# Modules.net
KiCad netlist of a schematic drawn in Altium Designer
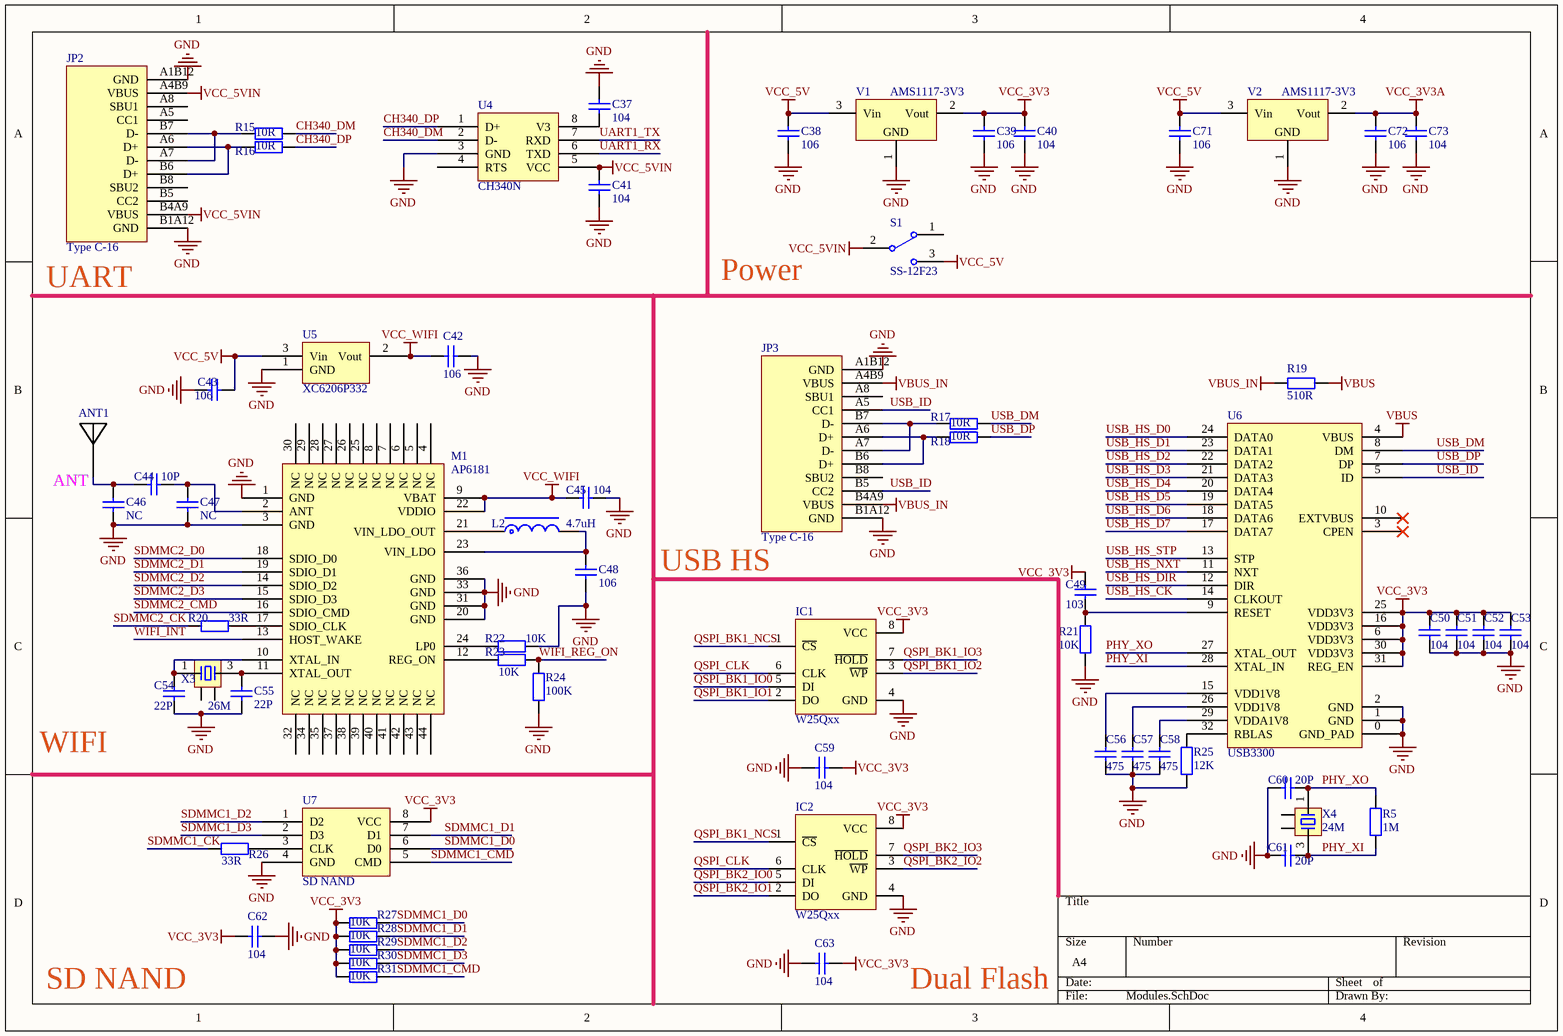
[diagram p0: Modules.SchDoc]

(export (version "E")
  (design (tool "Eeschema 10.0.6"))
  (components
    (comp (ref "ANT1") (value "ANT_SMD") (footprint "2.4G ANT") (libsource (lib "MySchlib") (part "ANT_SMD")))
    (comp (ref "C37")
      (value "104")
      (footprint "C0402_M")
      (description "贴片电容/MLCC电容")
      (libsource (lib "0.1 - 电阻-电容-电感-晶振-晶体-磁珠-电位器-法拉电容-馈通电容") (part "C"))
    )
    (comp (ref "C38")
      (value "106")
      (footprint "C1206_M")
      (description "贴片电容/MLCC电容")
      (libsource (lib "0.1 - 电阻-电容-电感-晶振-晶体-磁珠-电位器-法拉电容-馈通电容") (part "C"))
    )
    (comp (ref "C39")
      (value "106")
      (footprint "C0402_M")
      (description "贴片电容/MLCC电容")
      (libsource (lib "0.1 - 电阻-电容-电感-晶振-晶体-磁珠-电位器-法拉电容-馈通电容") (part "C"))
    )
    (comp (ref "C40")
      (value "104")
      (footprint "C0402_M")
      (description "贴片电容/MLCC电容")
      (libsource (lib "0.1 - 电阻-电容-电感-晶振-晶体-磁珠-电位器-法拉电容-馈通电容") (part "C"))
    )
    (comp (ref "C41")
      (value "104")
      (footprint "C0402_M")
      (description "贴片电容/MLCC电容")
      (libsource (lib "0.1 - 电阻-电容-电感-晶振-晶体-磁珠-电位器-法拉电容-馈通电容") (part "C"))
    )
    (comp (ref "C42")
      (value "106")
      (footprint "C0402_M")
      (description "贴片电容/MLCC电容")
      (libsource (lib "0.1 - 电阻-电容-电感-晶振-晶体-磁珠-电位器-法拉电容-馈通电容") (part "C"))
    )
    (comp (ref "C43")
      (value "106")
      (footprint "C0402_M")
      (description "贴片电容/MLCC电容")
      (libsource (lib "0.1 - 电阻-电容-电感-晶振-晶体-磁珠-电位器-法拉电容-馈通电容") (part "C"))
    )
    (comp (ref "C44")
      (value "10P")
      (footprint "C0402_M")
      (description "贴片电容/MLCC电容")
      (libsource (lib "0.1 - 电阻-电容-电感-晶振-晶体-磁珠-电位器-法拉电容-馈通电容") (part "C"))
    )
    (comp (ref "C45")
      (value "104")
      (footprint "C0402_M")
      (description "贴片电容/MLCC电容")
      (libsource (lib "0.1 - 电阻-电容-电感-晶振-晶体-磁珠-电位器-法拉电容-馈通电容") (part "C"))
    )
    (comp (ref "C46")
      (value "NC")
      (footprint "C0402_M")
      (description "贴片电容/MLCC电容")
      (libsource (lib "0.1 - 电阻-电容-电感-晶振-晶体-磁珠-电位器-法拉电容-馈通电容") (part "C"))
    )
    (comp (ref "C47")
      (value "NC")
      (footprint "C0402_M")
      (description "贴片电容/MLCC电容")
      (libsource (lib "0.1 - 电阻-电容-电感-晶振-晶体-磁珠-电位器-法拉电容-馈通电容") (part "C"))
    )
    (comp (ref "C48")
      (value "106")
      (footprint "C0402_M")
      (description "贴片电容/MLCC电容")
      (libsource (lib "0.1 - 电阻-电容-电感-晶振-晶体-磁珠-电位器-法拉电容-馈通电容") (part "C"))
    )
    (comp (ref "C49")
      (value "103")
      (footprint "C0402_M")
      (description "贴片电容/MLCC电容")
      (libsource (lib "0.1 - 电阻-电容-电感-晶振-晶体-磁珠-电位器-法拉电容-馈通电容") (part "C"))
    )
    (comp (ref "C50")
      (value "104")
      (footprint "C0402_M")
      (description "贴片电容/MLCC电容")
      (libsource (lib "0.1 - 电阻-电容-电感-晶振-晶体-磁珠-电位器-法拉电容-馈通电容") (part "C"))
    )
    (comp (ref "C51")
      (value "104")
      (footprint "C0402_M")
      (description "贴片电容/MLCC电容")
      (libsource (lib "0.1 - 电阻-电容-电感-晶振-晶体-磁珠-电位器-法拉电容-馈通电容") (part "C"))
    )
    (comp (ref "C52")
      (value "104")
      (footprint "C0402_M")
      (description "贴片电容/MLCC电容")
      (libsource (lib "0.1 - 电阻-电容-电感-晶振-晶体-磁珠-电位器-法拉电容-馈通电容") (part "C"))
    )
    (comp (ref "C53")
      (value "104")
      (footprint "C0402_M")
      (description "贴片电容/MLCC电容")
      (libsource (lib "0.1 - 电阻-电容-电感-晶振-晶体-磁珠-电位器-法拉电容-馈通电容") (part "C"))
    )
    (comp (ref "C54")
      (value "22P")
      (footprint "C0402_M")
      (description "贴片电容/MLCC电容")
      (libsource (lib "0.1 - 电阻-电容-电感-晶振-晶体-磁珠-电位器-法拉电容-馈通电容") (part "C"))
    )
    (comp (ref "C55")
      (value "22P")
      (footprint "C0402_M")
      (description "贴片电容/MLCC电容")
      (libsource (lib "0.1 - 电阻-电容-电感-晶振-晶体-磁珠-电位器-法拉电容-馈通电容") (part "C"))
    )
    (comp (ref "C56")
      (value "475")
      (footprint "C0402_M")
      (description "贴片电容/MLCC电容")
      (libsource (lib "0.1 - 电阻-电容-电感-晶振-晶体-磁珠-电位器-法拉电容-馈通电容") (part "C"))
    )
    (comp (ref "C57")
      (value "475")
      (footprint "C0402_M")
      (description "贴片电容/MLCC电容")
      (libsource (lib "0.1 - 电阻-电容-电感-晶振-晶体-磁珠-电位器-法拉电容-馈通电容") (part "C"))
    )
    (comp (ref "C58")
      (value "475")
      (footprint "C0402_M")
      (description "贴片电容/MLCC电容")
      (libsource (lib "0.1 - 电阻-电容-电感-晶振-晶体-磁珠-电位器-法拉电容-馈通电容") (part "C"))
    )
    (comp (ref "C59")
      (value "104")
      (footprint "C0402_M")
      (description "贴片电容/MLCC电容")
      (libsource (lib "0.1 - 电阻-电容-电感-晶振-晶体-磁珠-电位器-法拉电容-馈通电容") (part "C"))
    )
    (comp (ref "C60")
      (value "20P")
      (footprint "C0402_M")
      (description "贴片电容/MLCC电容")
      (libsource (lib "0.1 - 电阻-电容-电感-晶振-晶体-磁珠-电位器-法拉电容-馈通电容") (part "C"))
    )
    (comp (ref "C61")
      (value "20P")
      (footprint "C0402_M")
      (description "贴片电容/MLCC电容")
      (libsource (lib "0.1 - 电阻-电容-电感-晶振-晶体-磁珠-电位器-法拉电容-馈通电容") (part "C"))
    )
    (comp (ref "C62")
      (value "104")
      (footprint "C0402_M")
      (description "贴片电容/MLCC电容")
      (libsource (lib "0.1 - 电阻-电容-电感-晶振-晶体-磁珠-电位器-法拉电容-馈通电容") (part "C"))
    )
    (comp (ref "C63")
      (value "104")
      (footprint "C0402_M")
      (description "贴片电容/MLCC电容")
      (libsource (lib "0.1 - 电阻-电容-电感-晶振-晶体-磁珠-电位器-法拉电容-馈通电容") (part "C"))
    )
    (comp (ref "C71")
      (value "106")
      (footprint "C1206_M")
      (description "贴片电容/MLCC电容")
      (libsource (lib "0.1 - 电阻-电容-电感-晶振-晶体-磁珠-电位器-法拉电容-馈通电容") (part "C"))
    )
    (comp (ref "C72")
      (value "106")
      (footprint "C0402_M")
      (description "贴片电容/MLCC电容")
      (libsource (lib "0.1 - 电阻-电容-电感-晶振-晶体-磁珠-电位器-法拉电容-馈通电容") (part "C"))
    )
    (comp (ref "C73")
      (value "104")
      (footprint "C0402_M")
      (description "贴片电容/MLCC电容")
      (libsource (lib "0.1 - 电阻-电容-电感-晶振-晶体-磁珠-电位器-法拉电容-馈通电容") (part "C"))
    )
    (comp (ref "IC1")
      (value "W25Qxx")
      (footprint "SOP8W_N")
      (description "SPI Flash")
      (fields (field (name "版权归属") "封装库来自淘宝 ID：黄晶宝石"))
      (libsource (lib "1.0 - 常见芯片") (part "W25Q"))
    )
    (comp (ref "IC2")
      (value "W25Qxx")
      (footprint "SOP8W_N")
      (description "SPI Flash")
      (fields (field (name "版权归属") "封装库来自淘宝 ID：黄晶宝石"))
      (libsource (lib "1.0 - 常见芯片") (part "W25Q"))
    )
    (comp (ref "JP2") (value "Type C-16") (footprint "TypeC16") (libsource (lib "我的原理图库") (part "Type C-16")))
    (comp (ref "JP3") (value "Type C-16") (footprint "TypeC16") (libsource (lib "我的原理图库") (part "Type C-16")))
    (comp (ref "L2")
      (value "4.7uH")
      (footprint "L1210")
      (description "太诱-NR磁胶电感")
      (libsource (lib "0.1 - 电阻-电容-电感-晶振-晶体-磁珠-电位器-法拉电容-馈通电容") (part "L-NR"))
    )
    (comp (ref "M1")
      (value "AP6181")
      (footprint "AP6181")
      (description "SDIO WIFI模块")
      (libsource (lib "MySchlib") (part "AP6181"))
    )
    (comp (ref "R5")
      (value "1M")
      (footprint "R0402_M")
      (description "贴片电阻")
      (libsource (lib "0.1 - 电阻-电容-电感-晶振-晶体-磁珠-电位器-法拉电容-馈通电容") (part "R"))
    )
    (comp (ref "R15")
      (value "10R")
      (footprint "R0402_M")
      (description "贴片电阻")
      (libsource (lib "0.1 - 电阻-电容-电感-晶振-晶体-磁珠-电位器-法拉电容-馈通电容") (part "R"))
    )
    (comp (ref "R16")
      (value "10R")
      (footprint "R0402_M")
      (description "贴片电阻")
      (libsource (lib "0.1 - 电阻-电容-电感-晶振-晶体-磁珠-电位器-法拉电容-馈通电容") (part "R"))
    )
    (comp (ref "R17")
      (value "10R")
      (footprint "R0402_M")
      (description "贴片电阻")
      (libsource (lib "0.1 - 电阻-电容-电感-晶振-晶体-磁珠-电位器-法拉电容-馈通电容") (part "R"))
    )
    (comp (ref "R18")
      (value "10R")
      (footprint "R0402_M")
      (description "贴片电阻")
      (libsource (lib "0.1 - 电阻-电容-电感-晶振-晶体-磁珠-电位器-法拉电容-馈通电容") (part "R"))
    )
    (comp (ref "R19")
      (value "510R")
      (footprint "R0603_M")
      (description "贴片电阻")
      (libsource (lib "0.1 - 电阻-电容-电感-晶振-晶体-磁珠-电位器-法拉电容-馈通电容") (part "R"))
    )
    (comp (ref "R20")
      (value "33R")
      (footprint "R0402_M")
      (description "贴片电阻")
      (libsource (lib "0.1 - 电阻-电容-电感-晶振-晶体-磁珠-电位器-法拉电容-馈通电容") (part "R"))
    )
    (comp (ref "R21")
      (value "10K")
      (footprint "R0402_M")
      (description "贴片电阻")
      (libsource (lib "0.1 - 电阻-电容-电感-晶振-晶体-磁珠-电位器-法拉电容-馈通电容") (part "R"))
    )
    (comp (ref "R22")
      (value "10K")
      (footprint "R0402_M")
      (description "贴片电阻")
      (libsource (lib "0.1 - 电阻-电容-电感-晶振-晶体-磁珠-电位器-法拉电容-馈通电容") (part "R"))
    )
    (comp (ref "R23")
      (value "10K")
      (footprint "R0402_M")
      (description "贴片电阻")
      (libsource (lib "0.1 - 电阻-电容-电感-晶振-晶体-磁珠-电位器-法拉电容-馈通电容") (part "R"))
    )
    (comp (ref "R24")
      (value "100K")
      (footprint "R0402_M")
      (description "贴片电阻")
      (libsource (lib "0.1 - 电阻-电容-电感-晶振-晶体-磁珠-电位器-法拉电容-馈通电容") (part "R"))
    )
    (comp (ref "R25")
      (value "12K")
      (footprint "R0402_M")
      (description "贴片电阻")
      (libsource (lib "0.1 - 电阻-电容-电感-晶振-晶体-磁珠-电位器-法拉电容-馈通电容") (part "R"))
    )
    (comp (ref "R26")
      (value "33R")
      (footprint "R0402_M")
      (description "贴片电阻")
      (libsource (lib "0.1 - 电阻-电容-电感-晶振-晶体-磁珠-电位器-法拉电容-馈通电容") (part "R"))
    )
    (comp (ref "R27")
      (value "10K")
      (footprint "R0402_M")
      (description "贴片电阻")
      (libsource (lib "0.1 - 电阻-电容-电感-晶振-晶体-磁珠-电位器-法拉电容-馈通电容") (part "R"))
    )
    (comp (ref "R28")
      (value "10K")
      (footprint "R0402_M")
      (description "贴片电阻")
      (libsource (lib "0.1 - 电阻-电容-电感-晶振-晶体-磁珠-电位器-法拉电容-馈通电容") (part "R"))
    )
    (comp (ref "R29")
      (value "10K")
      (footprint "R0402_M")
      (description "贴片电阻")
      (libsource (lib "0.1 - 电阻-电容-电感-晶振-晶体-磁珠-电位器-法拉电容-馈通电容") (part "R"))
    )
    (comp (ref "R30")
      (value "10K")
      (footprint "R0402_M")
      (description "贴片电阻")
      (libsource (lib "0.1 - 电阻-电容-电感-晶振-晶体-磁珠-电位器-法拉电容-馈通电容") (part "R"))
    )
    (comp (ref "R31")
      (value "10K")
      (footprint "R0402_M")
      (description "贴片电阻")
      (libsource (lib "0.1 - 电阻-电容-电感-晶振-晶体-磁珠-电位器-法拉电容-馈通电容") (part "R"))
    )
    (comp (ref "S1")
      (value "SS-12F23")
      (footprint "MSK-12C01-07")
      (description "1路波动开关")
      (libsource (lib "0.5 - 按键_开关_蜂鸣器_保险丝_电池_测试点_Mark点_铜柱") (part "SSW-1P"))
    )
    (comp (ref "U4")
      (value "CH340N")
      (footprint "SOP8")
      (description "USB转UART芯片 8P")
      (libsource (lib "MySchlib") (part "CH340N"))
    )
    (comp (ref "U5")
      (value "XC6206P332")
      (footprint "SOT23-3N")
      (description "低压差LDO")
      (libsource (lib "MySchlib") (part "XC6206P332"))
    )
    (comp (ref "U6")
      (value "USB3300")
      (footprint "QFN32 5x5_M")
      (description "USB2.0 HS PHY")
      (libsource (lib "MySchlib") (part "USB3300"))
    )
    (comp (ref "U7")
      (value "SD NAND")
      (footprint "LGA8 6x8mm")
      (description "贴片式SD")
      (libsource (lib "MySchlib") (part "SD NAND"))
    )
    (comp (ref "V1")
      (value "AMS1117-3V3")
      (footprint "SOT89_N")
      (description "三端稳压芯片")
      (libsource (lib "0.7 - 电源类芯片") (part "AMS1117_SOT89"))
    )
    (comp (ref "V2")
      (value "AMS1117-3V3")
      (footprint "SOT89_N")
      (description "三端稳压芯片")
      (libsource (lib "0.7 - 电源类芯片") (part "AMS1117_SOT89"))
    )
    (comp (ref "X3")
      (value "26M")
      (footprint "XTAL-3225-4P")
      (description "4脚无源晶振(谐振器）")
      (libsource (lib "") (part "XTAL-4P_1"))
    )
    (comp (ref "X4")
      (value "24M")
      (footprint "XTAL-3225-4P")
      (description "4脚无源晶振(谐振器）")
      (libsource (lib "0.1 - 电阻-电容-电感-晶振-晶体-磁珠-电位器-法拉电容-馈通电容") (part "XTAL-4P"))
    )
  )
  (nets
    (net (code "1") (name "/CH340_DM") (class "Default")
      (node (ref "R15") (pin "1") (pinfunction "1_1") (pintype "passive"))
      (node (ref "U4") (pin "2") (pinfunction "D-_2") (pintype "passive"))
    )
    (net (code "2") (name "/CH340_DP") (class "Default")
      (node (ref "R16") (pin "1") (pinfunction "1_1") (pintype "passive"))
      (node (ref "U4") (pin "1") (pinfunction "D+_1") (pintype "passive"))
    )
    (net (code "3") (name "/PHY_XI") (class "Default")
      (node (ref "C61") (pin "2") (pinfunction "2_2") (pintype "passive"))
      (node (ref "R5") (pin "1") (pinfunction "1_1") (pintype "passive"))
      (node (ref "U6") (pin "28") (pinfunction "XTAL_IN_28") (pintype "passive"))
      (node (ref "X4") (pin "3") (pinfunction "3_3") (pintype "passive"))
    )
    (net (code "4") (name "/PHY_XO") (class "Default")
      (node (ref "C60") (pin "2") (pinfunction "2_2") (pintype "passive"))
      (node (ref "R5") (pin "2") (pinfunction "2_2") (pintype "passive"))
      (node (ref "U6") (pin "27") (pinfunction "XTAL_OUT_27") (pintype "passive"))
      (node (ref "X4") (pin "1") (pinfunction "1_1") (pintype "passive"))
    )
    (net (code "5") (name "/QSPI_BK1_IO0") (class "Default")
      (node (ref "IC1") (pin "5") (pinfunction "DI_5") (pintype "passive"))
    )
    (net (code "6") (name "/QSPI_BK1_IO1") (class "Default")
      (node (ref "IC1") (pin "2") (pinfunction "DO_2") (pintype "passive"))
    )
    (net (code "7") (name "/QSPI_BK1_IO2") (class "Default")
      (node (ref "IC1") (pin "3") (pinfunction "~{WP}_3") (pintype "passive"))
    )
    (net (code "8") (name "/QSPI_BK1_IO3") (class "Default")
      (node (ref "IC1") (pin "7") (pinfunction "~{HOLD}_7") (pintype "passive"))
    )
    (net (code "9") (name "/QSPI_BK1_NCS") (class "Default")
      (node (ref "IC1") (pin "1") (pinfunction "~{CS}_1") (pintype "passive"))
      (node (ref "IC2") (pin "1") (pinfunction "~{CS}_1") (pintype "passive"))
    )
    (net (code "10") (name "/QSPI_BK2_IO0") (class "Default")
      (node (ref "IC2") (pin "5") (pinfunction "DI_5") (pintype "passive"))
    )
    (net (code "11") (name "/QSPI_BK2_IO1") (class "Default")
      (node (ref "IC2") (pin "2") (pinfunction "DO_2") (pintype "passive"))
    )
    (net (code "12") (name "/QSPI_BK2_IO2") (class "Default")
      (node (ref "IC2") (pin "3") (pinfunction "~{WP}_3") (pintype "passive"))
    )
    (net (code "13") (name "/QSPI_BK2_IO3") (class "Default")
      (node (ref "IC2") (pin "7") (pinfunction "~{HOLD}_7") (pintype "passive"))
    )
    (net (code "14") (name "/QSPI_CLK") (class "Default")
      (node (ref "IC1") (pin "6") (pinfunction "CLK_6") (pintype "passive"))
      (node (ref "IC2") (pin "6") (pinfunction "CLK_6") (pintype "passive"))
    )
    (net (code "15") (name "/SDMMC1_CK") (class "Default")
      (node (ref "R26") (pin "2") (pinfunction "2_2") (pintype "passive"))
    )
    (net (code "16") (name "/SDMMC1_CMD") (class "Default")
      (node (ref "R31") (pin "1") (pinfunction "1_1") (pintype "passive"))
      (node (ref "U7") (pin "5") (pinfunction "CMD_5") (pintype "passive"))
    )
    (net (code "17") (name "/SDMMC1_D0") (class "Default")
      (node (ref "R27") (pin "1") (pinfunction "1_1") (pintype "passive"))
      (node (ref "U7") (pin "6") (pinfunction "D0_6") (pintype "passive"))
    )
    (net (code "18") (name "/SDMMC1_D1") (class "Default")
      (node (ref "R28") (pin "1") (pinfunction "1_1") (pintype "passive"))
      (node (ref "U7") (pin "7") (pinfunction "D1_7") (pintype "passive"))
    )
    (net (code "19") (name "/SDMMC1_D2") (class "Default")
      (node (ref "R29") (pin "1") (pinfunction "1_1") (pintype "passive"))
      (node (ref "U7") (pin "1") (pinfunction "D2_1") (pintype "passive"))
    )
    (net (code "20") (name "/SDMMC1_D3") (class "Default")
      (node (ref "R30") (pin "1") (pinfunction "1_1") (pintype "passive"))
      (node (ref "U7") (pin "2") (pinfunction "D3_2") (pintype "passive"))
    )
    (net (code "21") (name "/SDMMC2_CK") (class "Default")
      (node (ref "R20") (pin "2") (pinfunction "2_2") (pintype "passive"))
    )
    (net (code "22") (name "/SDMMC2_CMD") (class "Default")
      (node (ref "M1") (pin "16") (pinfunction "SDIO_CMD_16") (pintype "tri_state"))
    )
    (net (code "23") (name "/SDMMC2_D0") (class "Default")
      (node (ref "M1") (pin "18") (pinfunction "SDIO_D0_18") (pintype "tri_state"))
    )
    (net (code "24") (name "/SDMMC2_D1") (class "Default")
      (node (ref "M1") (pin "19") (pinfunction "SDIO_D1_19") (pintype "passive"))
    )
    (net (code "25") (name "/SDMMC2_D2") (class "Default")
      (node (ref "M1") (pin "14") (pinfunction "SDIO_D2_14") (pintype "tri_state"))
    )
    (net (code "26") (name "/SDMMC2_D3") (class "Default")
      (node (ref "M1") (pin "15") (pinfunction "SDIO_D3_15") (pintype "tri_state"))
    )
    (net (code "27") (name "/UART1_RX") (class "Default")
      (node (ref "U4") (pin "6") (pinfunction "TXD_6") (pintype "passive"))
    )
    (net (code "28") (name "/UART1_TX") (class "Default")
      (node (ref "U4") (pin "7") (pinfunction "RXD_7") (pintype "passive"))
    )
    (net (code "29") (name "/USB_DM") (class "Default")
      (node (ref "R17") (pin "1") (pinfunction "1_1") (pintype "passive"))
      (node (ref "U6") (pin "8") (pinfunction "DM_8") (pintype "passive"))
    )
    (net (code "30") (name "/USB_DP") (class "Default")
      (node (ref "R18") (pin "1") (pinfunction "1_1") (pintype "passive"))
      (node (ref "U6") (pin "7") (pinfunction "DP_7") (pintype "passive"))
    )
    (net (code "31") (name "/USB_HS_CK") (class "Default")
      (node (ref "U6") (pin "14") (pinfunction "CLKOUT_14") (pintype "passive"))
    )
    (net (code "32") (name "/USB_HS_D0") (class "Default")
      (node (ref "U6") (pin "24") (pinfunction "DATA0_24") (pintype "passive"))
    )
    (net (code "33") (name "/USB_HS_D1") (class "Default")
      (node (ref "U6") (pin "23") (pinfunction "DATA1_23") (pintype "passive"))
    )
    (net (code "34") (name "/USB_HS_D2") (class "Default")
      (node (ref "U6") (pin "22") (pinfunction "DATA2_22") (pintype "passive"))
    )
    (net (code "35") (name "/USB_HS_D3") (class "Default")
      (node (ref "U6") (pin "21") (pinfunction "DATA3_21") (pintype "passive"))
    )
    (net (code "36") (name "/USB_HS_D4") (class "Default")
      (node (ref "U6") (pin "20") (pinfunction "DATA4_20") (pintype "passive"))
    )
    (net (code "37") (name "/USB_HS_D5") (class "Default")
      (node (ref "U6") (pin "19") (pinfunction "DATA5_19") (pintype "passive"))
    )
    (net (code "38") (name "/USB_HS_D6") (class "Default")
      (node (ref "U6") (pin "18") (pinfunction "DATA6_18") (pintype "passive"))
    )
    (net (code "39") (name "/USB_HS_D7") (class "Default")
      (node (ref "U6") (pin "17") (pinfunction "DATA7_17") (pintype "passive"))
    )
    (net (code "40") (name "/USB_HS_DIR") (class "Default")
      (node (ref "U6") (pin "12") (pinfunction "DIR_12") (pintype "passive"))
    )
    (net (code "41") (name "/USB_HS_NXT") (class "Default")
      (node (ref "U6") (pin "11") (pinfunction "NXT_11") (pintype "passive"))
    )
    (net (code "42") (name "/USB_HS_STP") (class "Default")
      (node (ref "U6") (pin "13") (pinfunction "STP_13") (pintype "passive"))
    )
    (net (code "43") (name "/USB_ID") (class "Default")
      (node (ref "JP3") (pin "A5") (pinfunction "CC1_A5") (pintype "passive"))
      (node (ref "JP3") (pin "B5") (pinfunction "CC2_B5") (pintype "passive"))
      (node (ref "U6") (pin "5") (pinfunction "ID_5") (pintype "passive"))
    )
    (net (code "44") (name "/WIFI_INT") (class "Default")
      (node (ref "M1") (pin "13") (pinfunction "HOST_WAKE_13") (pintype "tri_state"))
    )
    (net (code "45") (name "/WIFI_REG_ON") (class "Default")
      (node (ref "R23") (pin "1") (pinfunction "1_1") (pintype "passive"))
      (node (ref "R24") (pin "1") (pinfunction "1_1") (pintype "passive"))
    )
    (net (code "46") (name "GND") (class "Default")
      (node (ref "C37") (pin "2") (pinfunction "2_2") (pintype "passive"))
      (node (ref "C38") (pin "1") (pinfunction "1_1") (pintype "passive"))
      (node (ref "C39") (pin "1") (pinfunction "1_1") (pintype "passive"))
      (node (ref "C40") (pin "1") (pinfunction "1_1") (pintype "passive"))
      (node (ref "C41") (pin "1") (pinfunction "1_1") (pintype "passive"))
      (node (ref "C42") (pin "1") (pinfunction "1_1") (pintype "passive"))
      (node (ref "C43") (pin "2") (pinfunction "2_2") (pintype "passive"))
      (node (ref "C45") (pin "1") (pinfunction "1_1") (pintype "passive"))
      (node (ref "C46") (pin "2") (pinfunction "2_2") (pintype "passive"))
      (node (ref "C47") (pin "2") (pinfunction "2_2") (pintype "passive"))
      (node (ref "C48") (pin "1") (pinfunction "1_1") (pintype "passive"))
      (node (ref "C50") (pin "1") (pinfunction "1_1") (pintype "passive"))
      (node (ref "C51") (pin "1") (pinfunction "1_1") (pintype "passive"))
      (node (ref "C52") (pin "1") (pinfunction "1_1") (pintype "passive"))
      (node (ref "C53") (pin "1") (pinfunction "1_1") (pintype "passive"))
      (node (ref "C54") (pin "1") (pinfunction "1_1") (pintype "passive"))
      (node (ref "C55") (pin "1") (pinfunction "1_1") (pintype "passive"))
      (node (ref "C56") (pin "1") (pinfunction "1_1") (pintype "passive"))
      (node (ref "C57") (pin "1") (pinfunction "1_1") (pintype "passive"))
      (node (ref "C58") (pin "1") (pinfunction "1_1") (pintype "passive"))
      (node (ref "C59") (pin "1") (pinfunction "1_1") (pintype "passive"))
      (node (ref "C60") (pin "1") (pinfunction "1_1") (pintype "passive"))
      (node (ref "C61") (pin "1") (pinfunction "1_1") (pintype "passive"))
      (node (ref "C62") (pin "1") (pinfunction "1_1") (pintype "passive"))
      (node (ref "C63") (pin "1") (pinfunction "1_1") (pintype "passive"))
      (node (ref "C71") (pin "1") (pinfunction "1_1") (pintype "passive"))
      (node (ref "C72") (pin "1") (pinfunction "1_1") (pintype "passive"))
      (node (ref "C73") (pin "1") (pinfunction "1_1") (pintype "passive"))
      (node (ref "IC1") (pin "4") (pinfunction "GND_4") (pintype "passive"))
      (node (ref "IC2") (pin "4") (pinfunction "GND_4") (pintype "passive"))
      (node (ref "JP2") (pin "A1B12") (pinfunction "GND_A1B12") (pintype "passive"))
      (node (ref "JP2") (pin "B1A12") (pinfunction "GND_B1A12") (pintype "passive"))
      (node (ref "JP3") (pin "A1B12") (pinfunction "GND_A1B12") (pintype "passive"))
      (node (ref "JP3") (pin "B1A12") (pinfunction "GND_B1A12") (pintype "passive"))
      (node (ref "M1") (pin "1") (pinfunction "GND_1") (pintype "passive"))
      (node (ref "M1") (pin "20") (pinfunction "GND_20") (pintype "passive"))
      (node (ref "M1") (pin "3") (pinfunction "GND_3") (pintype "passive"))
      (node (ref "M1") (pin "31") (pinfunction "GND_31") (pintype "passive"))
      (node (ref "M1") (pin "33") (pinfunction "GND_33") (pintype "passive"))
      (node (ref "M1") (pin "36") (pinfunction "GND_36") (pintype "passive"))
      (node (ref "R21") (pin "1") (pinfunction "1_1") (pintype "passive"))
      (node (ref "R22") (pin "1") (pinfunction "1_1") (pintype "passive"))
      (node (ref "R24") (pin "2") (pinfunction "2_2") (pintype "passive"))
      (node (ref "R25") (pin "2") (pinfunction "2_2") (pintype "passive"))
      (node (ref "U4") (pin "3") (pinfunction "GND_3") (pintype "passive"))
      (node (ref "U5") (pin "1") (pinfunction "GND_1") (pintype "passive"))
      (node (ref "U6") (pin "0") (pinfunction "GND_PAD_0") (pintype "passive"))
      (node (ref "U6") (pin "1") (pinfunction "GND_1") (pintype "passive"))
      (node (ref "U6") (pin "2") (pinfunction "GND_2") (pintype "passive"))
      (node (ref "U7") (pin "4") (pinfunction "GND_4") (pintype "passive"))
      (node (ref "V1") (pin "1") (pinfunction "GND_1") (pintype "passive"))
      (node (ref "V2") (pin "1") (pinfunction "GND_1") (pintype "passive"))
    )
    (net (code "47") (name "Net-(ANT1-Pad1)") (class "Default")
      (node (ref "ANT1") (pin "1") (pinfunction "1_1") (pintype "passive"))
      (node (ref "C44") (pin "2") (pinfunction "2_2") (pintype "passive"))
      (node (ref "C46") (pin "1") (pinfunction "1_1") (pintype "passive"))
    )
    (net (code "48") (name "Net-(C56-Pad2)") (class "Default")
      (node (ref "C56") (pin "2") (pinfunction "2_2") (pintype "passive"))
      (node (ref "U6") (pin "15") (pinfunction "VDD1V8_15") (pintype "passive"))
    )
    (net (code "49") (name "Net-(C57-Pad2)") (class "Default")
      (node (ref "C57") (pin "2") (pinfunction "2_2") (pintype "passive"))
      (node (ref "U6") (pin "26") (pinfunction "VDD1V8_26") (pintype "passive"))
    )
    (net (code "50") (name "Net-(JP2-D+-PadA6)") (class "Default")
      (node (ref "JP2") (pin "A6") (pinfunction "D+_A6") (pintype "passive"))
      (node (ref "JP2") (pin "B6") (pinfunction "D+_B6") (pintype "passive"))
      (node (ref "R16") (pin "2") (pinfunction "2_2") (pintype "passive"))
    )
    (net (code "51") (name "Net-(JP2-D--PadA7)") (class "Default")
      (node (ref "JP2") (pin "A7") (pinfunction "D-_A7") (pintype "passive"))
      (node (ref "JP2") (pin "B7") (pinfunction "D-_B7") (pintype "passive"))
      (node (ref "R15") (pin "2") (pinfunction "2_2") (pintype "passive"))
    )
    (net (code "52") (name "Net-(JP3-D+-PadA6)") (class "Default")
      (node (ref "JP3") (pin "A6") (pinfunction "D+_A6") (pintype "passive"))
      (node (ref "JP3") (pin "B6") (pinfunction "D+_B6") (pintype "passive"))
      (node (ref "R18") (pin "2") (pinfunction "2_2") (pintype "passive"))
    )
    (net (code "53") (name "Net-(JP3-D--PadA7)") (class "Default")
      (node (ref "JP3") (pin "A7") (pinfunction "D-_A7") (pintype "passive"))
      (node (ref "JP3") (pin "B7") (pinfunction "D-_B7") (pintype "passive"))
      (node (ref "R17") (pin "2") (pinfunction "2_2") (pintype "passive"))
    )
    (net (code "54") (name "Net-(M1-ANT)") (class "Default")
      (node (ref "C44") (pin "1") (pinfunction "1_1") (pintype "passive"))
      (node (ref "C47") (pin "1") (pinfunction "1_1") (pintype "passive"))
      (node (ref "M1") (pin "2") (pinfunction "ANT_2") (pintype "tri_state"))
    )
    (net (code "55") (name "Net-(M1-LP0)") (class "Default")
      (node (ref "M1") (pin "24") (pinfunction "LP0_24") (pintype "tri_state"))
      (node (ref "R22") (pin "2") (pinfunction "2_2") (pintype "passive"))
    )
    (net (code "56") (name "Net-(M1-REG_ON)") (class "Default")
      (node (ref "M1") (pin "12") (pinfunction "REG_ON_12") (pintype "tri_state"))
      (node (ref "R23") (pin "2") (pinfunction "2_2") (pintype "passive"))
    )
    (net (code "57") (name "Net-(M1-SDIO_CLK)") (class "Default")
      (node (ref "M1") (pin "17") (pinfunction "SDIO_CLK_17") (pintype "tri_state"))
      (node (ref "R20") (pin "1") (pinfunction "1_1") (pintype "passive"))
    )
    (net (code "58") (name "Net-(M1-VIN_LDO)") (class "Default")
      (node (ref "C48") (pin "2") (pinfunction "2_2") (pintype "passive"))
      (node (ref "L2") (pin "2") (pinfunction "2_2") (pintype "passive"))
      (node (ref "M1") (pin "23") (pinfunction "VIN_LDO_23") (pintype "passive"))
    )
    (net (code "59") (name "Net-(M1-VIN_LDO_OUT)") (class "Default")
      (node (ref "L2") (pin "1") (pinfunction "1_1") (pintype "passive"))
      (node (ref "M1") (pin "21") (pinfunction "VIN_LDO_OUT_21") (pintype "passive"))
    )
    (net (code "60") (name "Net-(M1-XTAL_IN)") (class "Default")
      (node (ref "C54") (pin "2") (pinfunction "2_2") (pintype "passive"))
      (node (ref "M1") (pin "10") (pinfunction "XTAL_IN_10") (pintype "tri_state"))
      (node (ref "X3") (pin "1") (pinfunction "1_1") (pintype "passive"))
    )
    (net (code "61") (name "Net-(M1-XTAL_OUT)") (class "Default")
      (node (ref "C55") (pin "2") (pinfunction "2_2") (pintype "passive"))
      (node (ref "M1") (pin "11") (pinfunction "XTAL_OUT_11") (pintype "tri_state"))
      (node (ref "X3") (pin "3") (pinfunction "3_3") (pintype "passive"))
    )
    (net (code "62") (name "Net-(U4-V3)") (class "Default")
      (node (ref "C37") (pin "1") (pinfunction "1_1") (pintype "passive"))
      (node (ref "U4") (pin "8") (pinfunction "V3_8") (pintype "passive"))
    )
    (net (code "63") (name "Net-(U6-RBLAS)") (class "Default")
      (node (ref "R25") (pin "1") (pinfunction "1_1") (pintype "passive"))
      (node (ref "U6") (pin "32") (pinfunction "RBLAS_32") (pintype "passive"))
    )
    (net (code "64") (name "Net-(U6-RESET)") (class "Default")
      (node (ref "C49") (pin "1") (pinfunction "1_1") (pintype "passive"))
      (node (ref "R21") (pin "2") (pinfunction "2_2") (pintype "passive"))
      (node (ref "U6") (pin "9") (pinfunction "RESET_9") (pintype "passive"))
    )
    (net (code "65") (name "Net-(U6-VDDA1V8)") (class "Default")
      (node (ref "C58") (pin "2") (pinfunction "2_2") (pintype "passive"))
      (node (ref "U6") (pin "29") (pinfunction "VDDA1V8_29") (pintype "passive"))
    )
    (net (code "66") (name "Net-(U7-CLK)") (class "Default")
      (node (ref "R26") (pin "1") (pinfunction "1_1") (pintype "passive"))
      (node (ref "U7") (pin "3") (pinfunction "CLK_3") (pintype "passive"))
    )
    (net (code "67") (name "VBUS") (class "Default")
      (node (ref "R19") (pin "1") (pinfunction "1_1") (pintype "passive"))
      (node (ref "U6") (pin "4") (pinfunction "VBUS_4") (pintype "passive"))
    )
    (net (code "68") (name "VBUS_IN") (class "Default")
      (node (ref "JP3") (pin "A4B9") (pinfunction "VBUS_A4B9") (pintype "passive"))
      (node (ref "JP3") (pin "B4A9") (pinfunction "VBUS_B4A9") (pintype "passive"))
      (node (ref "R19") (pin "2") (pinfunction "2_2") (pintype "passive"))
    )
    (net (code "69") (name "VCC_3V3") (class "Default")
      (node (ref "C39") (pin "2") (pinfunction "2_2") (pintype "passive"))
      (node (ref "C40") (pin "2") (pinfunction "2_2") (pintype "passive"))
      (node (ref "C49") (pin "2") (pinfunction "2_2") (pintype "passive"))
      (node (ref "C50") (pin "2") (pinfunction "2_2") (pintype "passive"))
      (node (ref "C51") (pin "2") (pinfunction "2_2") (pintype "passive"))
      (node (ref "C52") (pin "2") (pinfunction "2_2") (pintype "passive"))
      (node (ref "C53") (pin "2") (pinfunction "2_2") (pintype "passive"))
      (node (ref "C59") (pin "2") (pinfunction "2_2") (pintype "passive"))
      (node (ref "C62") (pin "2") (pinfunction "2_2") (pintype "passive"))
      (node (ref "C63") (pin "2") (pinfunction "2_2") (pintype "passive"))
      (node (ref "IC1") (pin "8") (pinfunction "VCC_8") (pintype "passive"))
      (node (ref "IC2") (pin "8") (pinfunction "VCC_8") (pintype "passive"))
      (node (ref "R27") (pin "2") (pinfunction "2_2") (pintype "passive"))
      (node (ref "R28") (pin "2") (pinfunction "2_2") (pintype "passive"))
      (node (ref "R29") (pin "2") (pinfunction "2_2") (pintype "passive"))
      (node (ref "R30") (pin "2") (pinfunction "2_2") (pintype "passive"))
      (node (ref "R31") (pin "2") (pinfunction "2_2") (pintype "passive"))
      (node (ref "U6") (pin "16") (pinfunction "VDD3V3_16") (pintype "passive"))
      (node (ref "U6") (pin "25") (pinfunction "VDD3V3_25") (pintype "passive"))
      (node (ref "U6") (pin "30") (pinfunction "VDD3V3_30") (pintype "passive"))
      (node (ref "U6") (pin "31") (pinfunction "REG_EN_31") (pintype "passive"))
      (node (ref "U6") (pin "6") (pinfunction "VDD3V3_6") (pintype "passive"))
      (node (ref "U7") (pin "8") (pinfunction "VCC_8") (pintype "passive"))
      (node (ref "V1") (pin "2") (pinfunction "Vout_2") (pintype "passive"))
    )
    (net (code "70") (name "VCC_3V3A") (class "Default")
      (node (ref "C72") (pin "2") (pinfunction "2_2") (pintype "passive"))
      (node (ref "C73") (pin "2") (pinfunction "2_2") (pintype "passive"))
      (node (ref "V2") (pin "2") (pinfunction "Vout_2") (pintype "passive"))
    )
    (net (code "71") (name "VCC_5V") (class "Default")
      (node (ref "C38") (pin "2") (pinfunction "2_2") (pintype "passive"))
      (node (ref "C43") (pin "1") (pinfunction "1_1") (pintype "passive"))
      (node (ref "C71") (pin "2") (pinfunction "2_2") (pintype "passive"))
      (node (ref "S1") (pin "3") (pinfunction "3_3") (pintype "passive"))
      (node (ref "U5") (pin "3") (pinfunction "Vin_3") (pintype "passive"))
      (node (ref "V1") (pin "3") (pinfunction "Vin_3") (pintype "passive"))
      (node (ref "V2") (pin "3") (pinfunction "Vin_3") (pintype "passive"))
    )
    (net (code "72") (name "VCC_5VIN") (class "Default")
      (node (ref "C41") (pin "2") (pinfunction "2_2") (pintype "passive"))
      (node (ref "JP2") (pin "A4B9") (pinfunction "VBUS_A4B9") (pintype "passive"))
      (node (ref "JP2") (pin "B4A9") (pinfunction "VBUS_B4A9") (pintype "passive"))
      (node (ref "S1") (pin "2") (pinfunction "2_2") (pintype "passive"))
      (node (ref "U4") (pin "5") (pinfunction "VCC_5") (pintype "passive"))
    )
    (net (code "73") (name "VCC_WIFI") (class "Default")
      (node (ref "C42") (pin "2") (pinfunction "2_2") (pintype "passive"))
      (node (ref "C45") (pin "2") (pinfunction "2_2") (pintype "passive"))
      (node (ref "M1") (pin "22") (pinfunction "VDDIO_22") (pintype "passive"))
      (node (ref "M1") (pin "9") (pinfunction "VBAT_9") (pintype "passive"))
      (node (ref "U5") (pin "2") (pinfunction "Vout_2") (pintype "passive"))
    )
    (net (code "74") (name "unconnected-(JP2-CC1-PadA5)") (class "Default")
      (node (ref "JP2") (pin "A5") (pinfunction "CC1_A5") (pintype "passive"))
    )
    (net (code "75") (name "unconnected-(JP2-CC2-PadB5)") (class "Default")
      (node (ref "JP2") (pin "B5") (pinfunction "CC2_B5") (pintype "passive"))
    )
    (net (code "76") (name "unconnected-(JP2-SBU1-PadA8)") (class "Default")
      (node (ref "JP2") (pin "A8") (pinfunction "SBU1_A8") (pintype "passive"))
    )
    (net (code "77") (name "unconnected-(JP2-SBU2-PadB8)") (class "Default")
      (node (ref "JP2") (pin "B8") (pinfunction "SBU2_B8") (pintype "passive"))
    )
    (net (code "78") (name "unconnected-(JP3-SBU1-PadA8)") (class "Default")
      (node (ref "JP3") (pin "A8") (pinfunction "SBU1_A8") (pintype "passive"))
    )
    (net (code "79") (name "unconnected-(JP3-SBU2-PadB8)") (class "Default")
      (node (ref "JP3") (pin "B8") (pinfunction "SBU2_B8") (pintype "passive"))
    )
    (net (code "80") (name "unconnected-(M1-NC-Pad4)") (class "Default")
      (node (ref "M1") (pin "4") (pinfunction "NC_4") (pintype "tri_state"))
    )
    (net (code "81") (name "unconnected-(M1-NC-Pad5)") (class "Default")
      (node (ref "M1") (pin "5") (pinfunction "NC_5") (pintype "tri_state"))
    )
    (net (code "82") (name "unconnected-(M1-NC-Pad6)") (class "Default")
      (node (ref "M1") (pin "6") (pinfunction "NC_6") (pintype "tri_state"))
    )
    (net (code "83") (name "unconnected-(M1-NC-Pad7)") (class "Default")
      (node (ref "M1") (pin "7") (pinfunction "NC_7") (pintype "tri_state"))
    )
    (net (code "84") (name "unconnected-(M1-NC-Pad8)") (class "Default")
      (node (ref "M1") (pin "8") (pinfunction "NC_8") (pintype "tri_state"))
    )
    (net (code "85") (name "unconnected-(M1-NC-Pad25)") (class "Default")
      (node (ref "M1") (pin "25") (pinfunction "NC_25") (pintype "tri_state"))
    )
    (net (code "86") (name "unconnected-(M1-NC-Pad26)") (class "Default")
      (node (ref "M1") (pin "26") (pinfunction "NC_26") (pintype "tri_state"))
    )
    (net (code "87") (name "unconnected-(M1-NC-Pad27)") (class "Default")
      (node (ref "M1") (pin "27") (pinfunction "NC_27") (pintype "tri_state"))
    )
    (net (code "88") (name "unconnected-(M1-NC-Pad28)") (class "Default")
      (node (ref "M1") (pin "28") (pinfunction "NC_28") (pintype "tri_state"))
    )
    (net (code "89") (name "unconnected-(M1-NC-Pad29)") (class "Default")
      (node (ref "M1") (pin "29") (pinfunction "NC_29") (pintype "tri_state"))
    )
    (net (code "90") (name "unconnected-(M1-NC-Pad30)") (class "Default")
      (node (ref "M1") (pin "30") (pinfunction "NC_30") (pintype "tri_state"))
    )
    (net (code "91") (name "unconnected-(M1-NC-Pad32)") (class "Default")
      (node (ref "M1") (pin "32") (pinfunction "NC_32") (pintype "tri_state"))
    )
    (net (code "92") (name "unconnected-(M1-NC-Pad34)") (class "Default")
      (node (ref "M1") (pin "34") (pinfunction "NC_34") (pintype "tri_state"))
    )
    (net (code "93") (name "unconnected-(M1-NC-Pad35)") (class "Default")
      (node (ref "M1") (pin "35") (pinfunction "NC_35") (pintype "tri_state"))
    )
    (net (code "94") (name "unconnected-(M1-NC-Pad37)") (class "Default")
      (node (ref "M1") (pin "37") (pinfunction "NC_37") (pintype "tri_state"))
    )
    (net (code "95") (name "unconnected-(M1-NC-Pad38)") (class "Default")
      (node (ref "M1") (pin "38") (pinfunction "NC_38") (pintype "tri_state"))
    )
    (net (code "96") (name "unconnected-(M1-NC-Pad39)") (class "Default")
      (node (ref "M1") (pin "39") (pinfunction "NC_39") (pintype "tri_state"))
    )
    (net (code "97") (name "unconnected-(M1-NC-Pad40)") (class "Default")
      (node (ref "M1") (pin "40") (pinfunction "NC_40") (pintype "tri_state"))
    )
    (net (code "98") (name "unconnected-(M1-NC-Pad41)") (class "Default")
      (node (ref "M1") (pin "41") (pinfunction "NC_41") (pintype "tri_state"))
    )
    (net (code "99") (name "unconnected-(M1-NC-Pad42)") (class "Default")
      (node (ref "M1") (pin "42") (pinfunction "NC_42") (pintype "tri_state"))
    )
    (net (code "100") (name "unconnected-(M1-NC-Pad43)") (class "Default")
      (node (ref "M1") (pin "43") (pinfunction "NC_43") (pintype "tri_state"))
    )
    (net (code "101") (name "unconnected-(M1-NC-Pad44)") (class "Default")
      (node (ref "M1") (pin "44") (pinfunction "NC_44") (pintype "tri_state"))
    )
    (net (code "102") (name "unconnected-(S1-Pad1)") (class "Default")
      (node (ref "S1") (pin "1") (pinfunction "1_1") (pintype "passive"))
    )
    (net (code "103") (name "unconnected-(U4-RTS-Pad4)") (class "Default")
      (node (ref "U4") (pin "4") (pinfunction "RTS_4") (pintype "passive"))
    )
    (net (code "104") (name "unconnected-(U6-CPEN-Pad3)") (class "Default")
      (node (ref "U6") (pin "3") (pinfunction "CPEN_3") (pintype "passive+no_connect"))
    )
    (net (code "105") (name "unconnected-(U6-EXTVBUS-Pad10)") (class "Default")
      (node (ref "U6") (pin "10") (pinfunction "EXTVBUS_10") (pintype "passive+no_connect"))
    )
    (net (code "106") (name "unconnected-(X3-Pad2)") (class "Default")
      (node (ref "X3") (pin "2") (pinfunction "2_2") (pintype "passive"))
    )
    (net (code "107") (name "unconnected-(X3-Pad4)") (class "Default")
      (node (ref "X3") (pin "4") (pinfunction "4_4") (pintype "passive"))
    )
    (net (code "108") (name "unconnected-(X4-Pad2)") (class "Default")
      (node (ref "X4") (pin "2") (pinfunction "2_2") (pintype "passive"))
    )
    (net (code "109") (name "unconnected-(X4-Pad4)") (class "Default")
      (node (ref "X4") (pin "4") (pinfunction "4_4") (pintype "passive"))
    )
  )
)
